# PSDT_Power_v1_0_0.net
KiCad netlist of a schematic drawn in Altium Designer
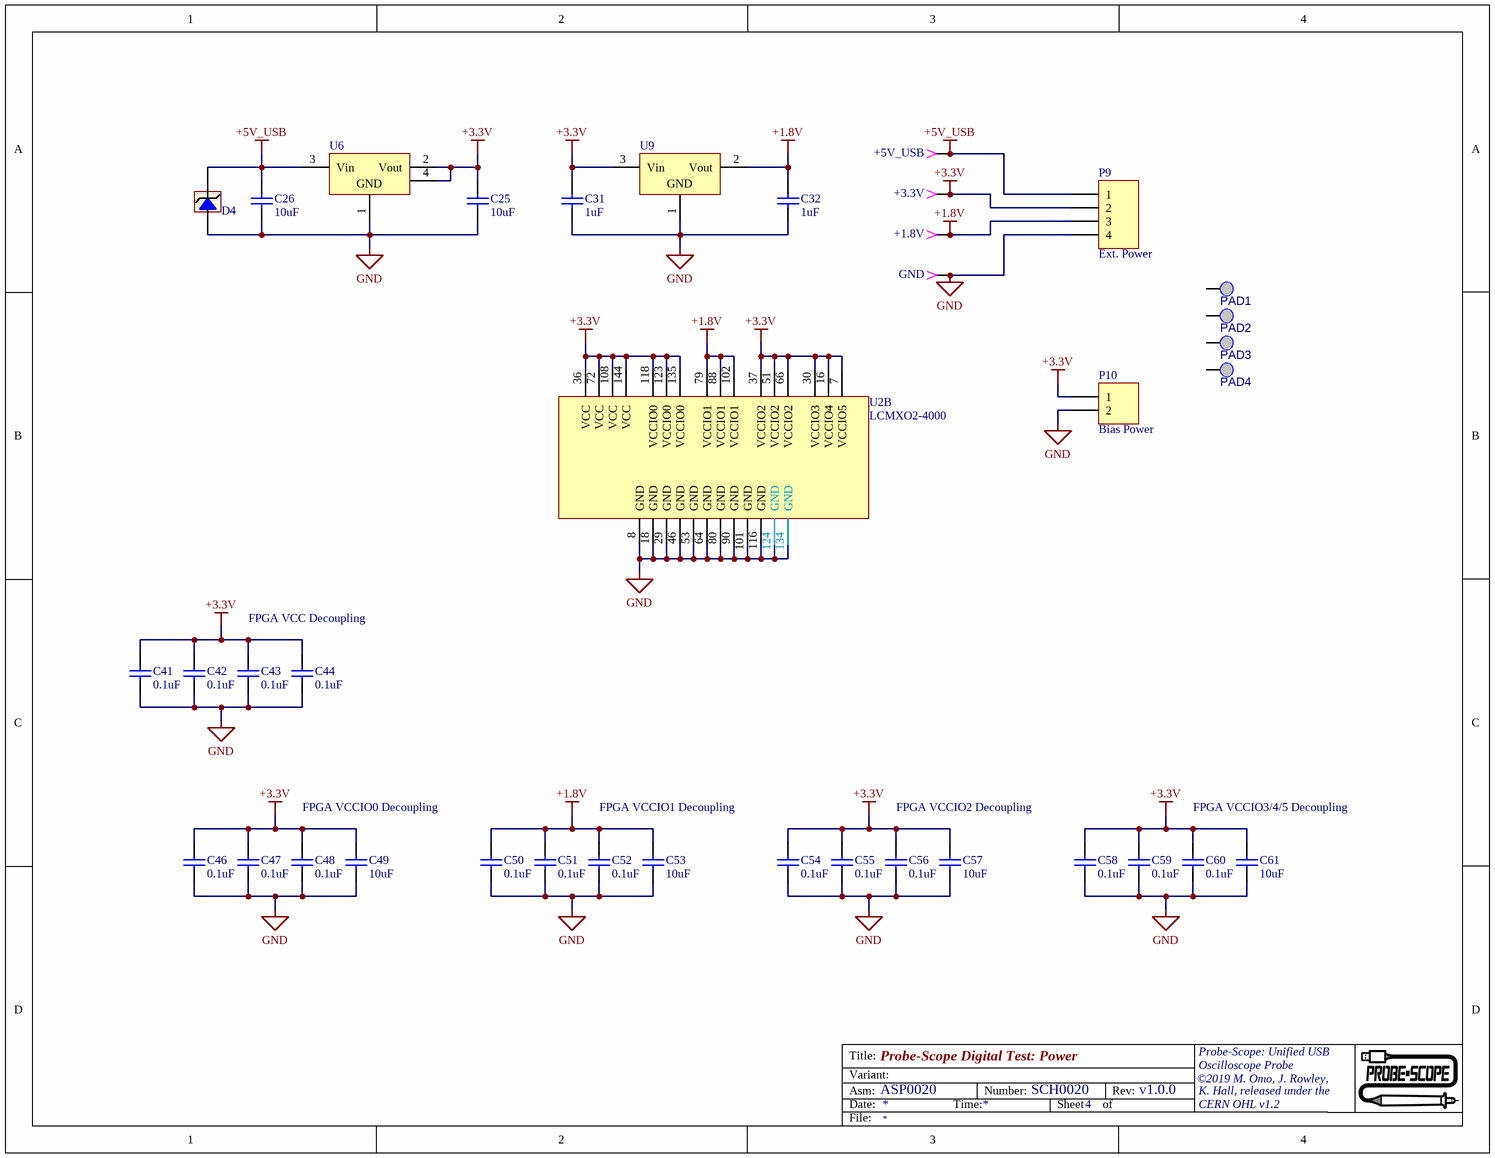
[diagram p0: PSDT Power v1.0.0.SchDoc]

(export (version "E")
  (design (tool "Eeschema 10.0.6"))
  (components
    (comp (ref "+1.8V")
      (value "TP")
      (footprint "TESTPOINT024")
      (fields
        (field (name "MANF") "Keystone Electronics")
        (field (name "APPROVED") "True")
        (field (name "MODIFIED BY") "sotterbacher")
      )
      (libsource (lib "MENG Database Library VPN") (part "TP"))
    )
    (comp (ref "+3.3V")
      (value "TP")
      (footprint "TESTPOINT024")
      (fields
        (field (name "MANF") "Keystone Electronics")
        (field (name "APPROVED") "True")
        (field (name "MODIFIED BY") "sotterbacher")
      )
      (libsource (lib "MENG Database Library VPN") (part "TP"))
    )
    (comp (ref "+5V_USB")
      (value "TP")
      (footprint "TESTPOINT024")
      (fields
        (field (name "MANF") "Keystone Electronics")
        (field (name "APPROVED") "True")
        (field (name "MODIFIED BY") "sotterbacher")
      )
      (libsource (lib "MENG Database Library VPN") (part "TP"))
    )
    (comp (ref "C25")
      (value "10uF")
      (footprint "0603(1608)")
      (fields
        (field (name "MANF") "Samsung Electro-Mechanics")
        (field (name "TOLERANCE") "20")
        (field (name "VOLTAGE") "25")
        (field (name "MODIFIED BY") "sotterbacher")
        (field (name "APPROVED") "True")
      )
      (libsource (lib "MENG Database Library VPN") (part "Cap"))
    )
    (comp (ref "C26")
      (value "10uF")
      (footprint "0603(1608)")
      (fields
        (field (name "MANF") "Samsung Electro-Mechanics")
        (field (name "TOLERANCE") "20")
        (field (name "VOLTAGE") "25")
        (field (name "MODIFIED BY") "sotterbacher")
        (field (name "APPROVED") "True")
      )
      (libsource (lib "MENG Database Library VPN") (part "Cap"))
    )
    (comp (ref "C31")
      (value "1uF")
      (footprint "0402(1005)")
      (fields
        (field (name "MANF") "Murata Electronics")
        (field (name "TOLERANCE") "10")
        (field (name "Comment") "10V")
        (field (name "MODIFIED BY") "jrowley")
        (field (name "APPROVED") "False")
      )
      (libsource (lib "MENG Database Library VPN") (part "Cap"))
    )
    (comp (ref "C32")
      (value "1uF")
      (footprint "0402(1005)")
      (fields
        (field (name "MANF") "Murata Electronics")
        (field (name "TOLERANCE") "10")
        (field (name "Comment") "10V")
        (field (name "MODIFIED BY") "jrowley")
        (field (name "APPROVED") "False")
      )
      (libsource (lib "MENG Database Library VPN") (part "Cap"))
    )
    (comp (ref "C41")
      (value "0.1uF")
      (footprint "0402(1005)")
      (fields
        (field (name "MANF") "Samsung Electro-Mechanics")
        (field (name "TOLERANCE") "10")
        (field (name "VOLTAGE") "6.3")
        (field (name "MODIFIED BY") "jrowley")
        (field (name "APPROVED") "False")
      )
      (libsource (lib "MENG Database Library VPN") (part "Cap"))
    )
    (comp (ref "C42")
      (value "0.1uF")
      (footprint "0402(1005)")
      (fields
        (field (name "MANF") "Samsung Electro-Mechanics")
        (field (name "TOLERANCE") "10")
        (field (name "VOLTAGE") "6.3")
        (field (name "MODIFIED BY") "jrowley")
        (field (name "APPROVED") "False")
      )
      (libsource (lib "MENG Database Library VPN") (part "Cap"))
    )
    (comp (ref "C43")
      (value "0.1uF")
      (footprint "0402(1005)")
      (fields
        (field (name "MANF") "Samsung Electro-Mechanics")
        (field (name "TOLERANCE") "10")
        (field (name "VOLTAGE") "6.3")
        (field (name "MODIFIED BY") "jrowley")
        (field (name "APPROVED") "False")
      )
      (libsource (lib "MENG Database Library VPN") (part "Cap"))
    )
    (comp (ref "C44")
      (value "0.1uF")
      (footprint "0402(1005)")
      (fields
        (field (name "MANF") "Samsung Electro-Mechanics")
        (field (name "TOLERANCE") "10")
        (field (name "VOLTAGE") "6.3")
        (field (name "MODIFIED BY") "jrowley")
        (field (name "APPROVED") "False")
      )
      (libsource (lib "MENG Database Library VPN") (part "Cap"))
    )
    (comp (ref "C46")
      (value "0.1uF")
      (footprint "0402(1005)")
      (fields
        (field (name "MANF") "Samsung Electro-Mechanics")
        (field (name "TOLERANCE") "10")
        (field (name "VOLTAGE") "6.3")
        (field (name "MODIFIED BY") "jrowley")
        (field (name "APPROVED") "False")
      )
      (libsource (lib "MENG Database Library VPN") (part "Cap"))
    )
    (comp (ref "C47")
      (value "0.1uF")
      (footprint "0402(1005)")
      (fields
        (field (name "MANF") "Samsung Electro-Mechanics")
        (field (name "TOLERANCE") "10")
        (field (name "VOLTAGE") "6.3")
        (field (name "MODIFIED BY") "jrowley")
        (field (name "APPROVED") "False")
      )
      (libsource (lib "MENG Database Library VPN") (part "Cap"))
    )
    (comp (ref "C48")
      (value "0.1uF")
      (footprint "0402(1005)")
      (fields
        (field (name "MANF") "Samsung Electro-Mechanics")
        (field (name "TOLERANCE") "10")
        (field (name "VOLTAGE") "6.3")
        (field (name "MODIFIED BY") "jrowley")
        (field (name "APPROVED") "False")
      )
      (libsource (lib "MENG Database Library VPN") (part "Cap"))
    )
    (comp (ref "C49")
      (value "10uF")
      (footprint "0603(1608)")
      (fields
        (field (name "MANF") "Samsung Electro-Mechanics")
        (field (name "TOLERANCE") "20")
        (field (name "VOLTAGE") "25")
        (field (name "MODIFIED BY") "sotterbacher")
        (field (name "APPROVED") "True")
      )
      (libsource (lib "MENG Database Library VPN") (part "Cap"))
    )
    (comp (ref "C50")
      (value "0.1uF")
      (footprint "0402(1005)")
      (fields
        (field (name "MANF") "Samsung Electro-Mechanics")
        (field (name "TOLERANCE") "10")
        (field (name "VOLTAGE") "6.3")
        (field (name "MODIFIED BY") "jrowley")
        (field (name "APPROVED") "False")
      )
      (libsource (lib "MENG Database Library VPN") (part "Cap"))
    )
    (comp (ref "C51")
      (value "0.1uF")
      (footprint "0402(1005)")
      (fields
        (field (name "MANF") "Samsung Electro-Mechanics")
        (field (name "TOLERANCE") "10")
        (field (name "VOLTAGE") "6.3")
        (field (name "MODIFIED BY") "jrowley")
        (field (name "APPROVED") "False")
      )
      (libsource (lib "MENG Database Library VPN") (part "Cap"))
    )
    (comp (ref "C52")
      (value "0.1uF")
      (footprint "0402(1005)")
      (fields
        (field (name "MANF") "Samsung Electro-Mechanics")
        (field (name "TOLERANCE") "10")
        (field (name "VOLTAGE") "6.3")
        (field (name "MODIFIED BY") "jrowley")
        (field (name "APPROVED") "False")
      )
      (libsource (lib "MENG Database Library VPN") (part "Cap"))
    )
    (comp (ref "C53")
      (value "10uF")
      (footprint "0603(1608)")
      (fields
        (field (name "MANF") "Samsung Electro-Mechanics")
        (field (name "TOLERANCE") "20")
        (field (name "VOLTAGE") "25")
        (field (name "MODIFIED BY") "sotterbacher")
        (field (name "APPROVED") "True")
      )
      (libsource (lib "MENG Database Library VPN") (part "Cap"))
    )
    (comp (ref "C54")
      (value "0.1uF")
      (footprint "0402(1005)")
      (fields
        (field (name "MANF") "Samsung Electro-Mechanics")
        (field (name "TOLERANCE") "10")
        (field (name "VOLTAGE") "6.3")
        (field (name "MODIFIED BY") "jrowley")
        (field (name "APPROVED") "False")
      )
      (libsource (lib "MENG Database Library VPN") (part "Cap"))
    )
    (comp (ref "C55")
      (value "0.1uF")
      (footprint "0402(1005)")
      (fields
        (field (name "MANF") "Samsung Electro-Mechanics")
        (field (name "TOLERANCE") "10")
        (field (name "VOLTAGE") "6.3")
        (field (name "MODIFIED BY") "jrowley")
        (field (name "APPROVED") "False")
      )
      (libsource (lib "MENG Database Library VPN") (part "Cap"))
    )
    (comp (ref "C56")
      (value "0.1uF")
      (footprint "0402(1005)")
      (fields
        (field (name "MANF") "Samsung Electro-Mechanics")
        (field (name "TOLERANCE") "10")
        (field (name "VOLTAGE") "6.3")
        (field (name "MODIFIED BY") "jrowley")
        (field (name "APPROVED") "False")
      )
      (libsource (lib "MENG Database Library VPN") (part "Cap"))
    )
    (comp (ref "C57")
      (value "10uF")
      (footprint "0603(1608)")
      (fields
        (field (name "MANF") "Samsung Electro-Mechanics")
        (field (name "TOLERANCE") "20")
        (field (name "VOLTAGE") "25")
        (field (name "MODIFIED BY") "sotterbacher")
        (field (name "APPROVED") "True")
      )
      (libsource (lib "MENG Database Library VPN") (part "Cap"))
    )
    (comp (ref "C58")
      (value "0.1uF")
      (footprint "0402(1005)")
      (fields
        (field (name "MANF") "Samsung Electro-Mechanics")
        (field (name "TOLERANCE") "10")
        (field (name "VOLTAGE") "6.3")
        (field (name "MODIFIED BY") "jrowley")
        (field (name "APPROVED") "False")
      )
      (libsource (lib "MENG Database Library VPN") (part "Cap"))
    )
    (comp (ref "C59")
      (value "0.1uF")
      (footprint "0402(1005)")
      (fields
        (field (name "MANF") "Samsung Electro-Mechanics")
        (field (name "TOLERANCE") "10")
        (field (name "VOLTAGE") "6.3")
        (field (name "MODIFIED BY") "jrowley")
        (field (name "APPROVED") "False")
      )
      (libsource (lib "MENG Database Library VPN") (part "Cap"))
    )
    (comp (ref "C60")
      (value "0.1uF")
      (footprint "0402(1005)")
      (fields
        (field (name "MANF") "Samsung Electro-Mechanics")
        (field (name "TOLERANCE") "10")
        (field (name "VOLTAGE") "6.3")
        (field (name "MODIFIED BY") "jrowley")
        (field (name "APPROVED") "False")
      )
      (libsource (lib "MENG Database Library VPN") (part "Cap"))
    )
    (comp (ref "C61")
      (value "10uF")
      (footprint "0603(1608)")
      (fields
        (field (name "MANF") "Samsung Electro-Mechanics")
        (field (name "TOLERANCE") "20")
        (field (name "VOLTAGE") "25")
        (field (name "MODIFIED BY") "sotterbacher")
        (field (name "APPROVED") "True")
      )
      (libsource (lib "MENG Database Library VPN") (part "Cap"))
    )
    (comp (ref "D4")
      (value "6.5V")
      (footprint "SMB NP")
      (fields
        (field (name "MANF") "Littelfuse")
        (field (name "VOLTAGE") "6.5")
        (field (name "POWER") "600")
        (field (name "MODIFIED BY") "tgage")
        (field (name "APPROVED") "True")
      )
      (libsource (lib "MENG Database Library VPN") (part "Transzorb"))
    )
    (comp (ref "GND")
      (value "TP")
      (footprint "TESTPOINT024")
      (fields
        (field (name "MANF") "Keystone Electronics")
        (field (name "MODIFIED BY") "sotterbacher")
        (field (name "APPROVED") "True")
      )
      (libsource (lib "MENG Database Library VPN") (part "TP"))
    )
    (comp (ref "P9")
      (value "Ext. Power")
      (footprint "0.1HDR1X4P")
      (fields
        (field (name "MANF") "Molex")
        (field (name "VOLTAGE") "250")
        (field (name "MODIFIED BY") "jrowley")
        (field (name "APPROVED") "False")
      )
      (libsource (lib "MENG Database Library VPN") (part "Header 4"))
    )
    (comp (ref "P10")
      (value "Bias Power")
      (footprint "0.1HDR1X2P")
      (fields
        (field (name "MANF") "Molex")
        (field (name "VOLTAGE") "250")
        (field (name "MODIFIED BY") "jrowley")
        (field (name "APPROVED") "False")
      )
      (libsource (lib "MENG Database Library VPN") (part "Header 2"))
    )
    (comp (ref "PAD1")
      (value "4-40 Loose")
      (footprint "PAD-4-40 Loose")
      (fields
        (field (name "MANF") "dummy")
        (field (name "MODIFIED BY") "pmarcus")
        (field (name "APPROVED") "True")
      )
      (libsource (lib "MENG Database Library VPN") (part "PAD"))
    )
    (comp (ref "PAD2")
      (value "4-40 Loose")
      (footprint "PAD-4-40 Loose")
      (fields
        (field (name "MANF") "dummy")
        (field (name "MODIFIED BY") "pmarcus")
        (field (name "APPROVED") "True")
      )
      (libsource (lib "MENG Database Library VPN") (part "PAD"))
    )
    (comp (ref "PAD3")
      (value "4-40 Loose")
      (footprint "PAD-4-40 Loose")
      (fields
        (field (name "MANF") "dummy")
        (field (name "MODIFIED BY") "pmarcus")
        (field (name "APPROVED") "True")
      )
      (libsource (lib "MENG Database Library VPN") (part "PAD"))
    )
    (comp (ref "PAD4")
      (value "4-40 Loose")
      (footprint "PAD-4-40 Loose")
      (fields
        (field (name "MANF") "dummy")
        (field (name "MODIFIED BY") "pmarcus")
        (field (name "APPROVED") "True")
      )
      (libsource (lib "MENG Database Library VPN") (part "PAD"))
    )
    (comp (ref "U2")
      (value "LCMXO2-4000")
      (footprint "UL_TQFP144")
      (fields (field (name "MANF") "Lattice Semiconductor Corporation"))
      (libsource (lib "PS") (part "MachXO2-4000-TG144"))
    )
    (comp (ref "U6")
      (value "LD1086D2M33TR")
      (footprint "D2PAK TO263-4N")
      (fields
        (field (name "MANF") "ST Microelectronics")
        (field (name "MODIFIED BY") "cschneiker")
        (field (name "APPROVED") "True")
      )
      (libsource (lib "MENG Database Library VPN") (part "Volt Reg 4"))
    )
    (comp (ref "U9")
      (value "1.8V")
      (footprint "SOT23-12-3TOP")
      (fields
        (field (name "MANF") "Microchip")
        (field (name "MODIFIED BY") "jrowley")
        (field (name "APPROVED") "False")
      )
      (libsource (lib "MENG Database Library VPN") (part "Volt Reg 7"))
    )
  )
  (nets
    (net (code "1") (name "+1.8V") (class "Default")
      (node (ref "+1.8V") (pin "1") (pinfunction "1_1") (pintype "passive"))
      (node (ref "C32") (pin "2") (pinfunction "2_2") (pintype "passive"))
      (node (ref "C50") (pin "2") (pinfunction "2_2") (pintype "passive"))
      (node (ref "C51") (pin "2") (pinfunction "2_2") (pintype "passive"))
      (node (ref "C52") (pin "2") (pinfunction "2_2") (pintype "passive"))
      (node (ref "C53") (pin "2") (pinfunction "2_2") (pintype "passive"))
      (node (ref "P9") (pin "3") (pinfunction "3_3") (pintype "passive"))
      (node (ref "U2") (pin "102") (pinfunction "VCCIO1_102") (pintype "power_in"))
      (node (ref "U2") (pin "79") (pinfunction "VCCIO1_79") (pintype "power_in"))
      (node (ref "U2") (pin "88") (pinfunction "VCCIO1_88") (pintype "power_in"))
      (node (ref "U9") (pin "2") (pinfunction "Vout_2") (pintype "passive"))
    )
    (net (code "2") (name "+3.3V") (class "Default")
      (node (ref "+3.3V") (pin "1") (pinfunction "1_1") (pintype "passive"))
      (node (ref "C25") (pin "2") (pinfunction "2_2") (pintype "passive"))
      (node (ref "C31") (pin "2") (pinfunction "2_2") (pintype "passive"))
      (node (ref "C41") (pin "2") (pinfunction "2_2") (pintype "passive"))
      (node (ref "C42") (pin "2") (pinfunction "2_2") (pintype "passive"))
      (node (ref "C43") (pin "2") (pinfunction "2_2") (pintype "passive"))
      (node (ref "C44") (pin "2") (pinfunction "2_2") (pintype "passive"))
      (node (ref "C46") (pin "2") (pinfunction "2_2") (pintype "passive"))
      (node (ref "C47") (pin "2") (pinfunction "2_2") (pintype "passive"))
      (node (ref "C48") (pin "2") (pinfunction "2_2") (pintype "passive"))
      (node (ref "C49") (pin "2") (pinfunction "2_2") (pintype "passive"))
      (node (ref "C54") (pin "2") (pinfunction "2_2") (pintype "passive"))
      (node (ref "C55") (pin "2") (pinfunction "2_2") (pintype "passive"))
      (node (ref "C56") (pin "2") (pinfunction "2_2") (pintype "passive"))
      (node (ref "C57") (pin "2") (pinfunction "2_2") (pintype "passive"))
      (node (ref "C58") (pin "2") (pinfunction "2_2") (pintype "passive"))
      (node (ref "C59") (pin "2") (pinfunction "2_2") (pintype "passive"))
      (node (ref "C60") (pin "2") (pinfunction "2_2") (pintype "passive"))
      (node (ref "C61") (pin "2") (pinfunction "2_2") (pintype "passive"))
      (node (ref "P10") (pin "1") (pinfunction "1_1") (pintype "passive"))
      (node (ref "P9") (pin "2") (pinfunction "2_2") (pintype "passive"))
      (node (ref "U2") (pin "108") (pinfunction "VCC_108") (pintype "power_in"))
      (node (ref "U2") (pin "118") (pinfunction "VCCIO0_118") (pintype "power_in"))
      (node (ref "U2") (pin "123") (pinfunction "VCCIO0_123") (pintype "power_in"))
      (node (ref "U2") (pin "135") (pinfunction "VCCIO0_135") (pintype "power_in"))
      (node (ref "U2") (pin "144") (pinfunction "VCC_144") (pintype "power_in"))
      (node (ref "U2") (pin "16") (pinfunction "VCCIO4_16") (pintype "power_in"))
      (node (ref "U2") (pin "30") (pinfunction "VCCIO3_30") (pintype "power_in"))
      (node (ref "U2") (pin "36") (pinfunction "VCC_36") (pintype "power_in"))
      (node (ref "U2") (pin "37") (pinfunction "VCCIO2_37") (pintype "power_in"))
      (node (ref "U2") (pin "51") (pinfunction "VCCIO2_51") (pintype "power_in"))
      (node (ref "U2") (pin "66") (pinfunction "VCCIO2_66") (pintype "power_in"))
      (node (ref "U2") (pin "7") (pinfunction "VCCIO5_7") (pintype "power_in"))
      (node (ref "U2") (pin "72") (pinfunction "VCC_72") (pintype "power_in"))
      (node (ref "U6") (pin "2") (pinfunction "Vout_2") (pintype "passive"))
      (node (ref "U6") (pin "4") (pinfunction "GND_4") (pintype "passive"))
      (node (ref "U9") (pin "3") (pinfunction "Vin_3") (pintype "passive"))
    )
    (net (code "3") (name "+5V_USB") (class "Default")
      (node (ref "+5V_USB") (pin "1") (pinfunction "1_1") (pintype "passive"))
      (node (ref "C26") (pin "2") (pinfunction "2_2") (pintype "passive"))
      (node (ref "D4") (pin "2") (pinfunction "2_2") (pintype "passive"))
      (node (ref "P9") (pin "1") (pinfunction "1_1") (pintype "passive"))
      (node (ref "U6") (pin "3") (pinfunction "Vin_3") (pintype "passive"))
    )
    (net (code "4") (name "GND") (class "Default")
      (node (ref "C25") (pin "1") (pinfunction "1_1") (pintype "passive"))
      (node (ref "C26") (pin "1") (pinfunction "1_1") (pintype "passive"))
      (node (ref "C31") (pin "1") (pinfunction "1_1") (pintype "passive"))
      (node (ref "C32") (pin "1") (pinfunction "1_1") (pintype "passive"))
      (node (ref "C41") (pin "1") (pinfunction "1_1") (pintype "passive"))
      (node (ref "C42") (pin "1") (pinfunction "1_1") (pintype "passive"))
      (node (ref "C43") (pin "1") (pinfunction "1_1") (pintype "passive"))
      (node (ref "C44") (pin "1") (pinfunction "1_1") (pintype "passive"))
      (node (ref "C46") (pin "1") (pinfunction "1_1") (pintype "passive"))
      (node (ref "C47") (pin "1") (pinfunction "1_1") (pintype "passive"))
      (node (ref "C48") (pin "1") (pinfunction "1_1") (pintype "passive"))
      (node (ref "C49") (pin "1") (pinfunction "1_1") (pintype "passive"))
      (node (ref "C50") (pin "1") (pinfunction "1_1") (pintype "passive"))
      (node (ref "C51") (pin "1") (pinfunction "1_1") (pintype "passive"))
      (node (ref "C52") (pin "1") (pinfunction "1_1") (pintype "passive"))
      (node (ref "C53") (pin "1") (pinfunction "1_1") (pintype "passive"))
      (node (ref "C54") (pin "1") (pinfunction "1_1") (pintype "passive"))
      (node (ref "C55") (pin "1") (pinfunction "1_1") (pintype "passive"))
      (node (ref "C56") (pin "1") (pinfunction "1_1") (pintype "passive"))
      (node (ref "C57") (pin "1") (pinfunction "1_1") (pintype "passive"))
      (node (ref "C58") (pin "1") (pinfunction "1_1") (pintype "passive"))
      (node (ref "C59") (pin "1") (pinfunction "1_1") (pintype "passive"))
      (node (ref "C60") (pin "1") (pinfunction "1_1") (pintype "passive"))
      (node (ref "C61") (pin "1") (pinfunction "1_1") (pintype "passive"))
      (node (ref "D4") (pin "1") (pinfunction "1_1") (pintype "passive"))
      (node (ref "GND") (pin "1") (pinfunction "1_1") (pintype "passive"))
      (node (ref "P10") (pin "2") (pinfunction "2_2") (pintype "passive"))
      (node (ref "P9") (pin "4") (pinfunction "4_4") (pintype "passive"))
      (node (ref "U2") (pin "101") (pinfunction "GND_101") (pintype "power_in"))
      (node (ref "U2") (pin "116") (pinfunction "GND_116") (pintype "power_in"))
      (node (ref "U2") (pin "124") (pinfunction "GND_124") (pintype "power_in"))
      (node (ref "U2") (pin "134") (pinfunction "GND_134") (pintype "power_in"))
      (node (ref "U2") (pin "18") (pinfunction "GND_18") (pintype "power_in"))
      (node (ref "U2") (pin "29") (pinfunction "GND_29") (pintype "power_in"))
      (node (ref "U2") (pin "46") (pinfunction "GND_46") (pintype "power_in"))
      (node (ref "U2") (pin "53") (pinfunction "GND_53") (pintype "power_in"))
      (node (ref "U2") (pin "64") (pinfunction "GND_64") (pintype "power_in"))
      (node (ref "U2") (pin "8") (pinfunction "GND_8") (pintype "power_in"))
      (node (ref "U2") (pin "80") (pinfunction "GND_80") (pintype "power_in"))
      (node (ref "U2") (pin "90") (pinfunction "GND_90") (pintype "power_in"))
      (node (ref "U6") (pin "1") (pinfunction "GND_1") (pintype "passive"))
      (node (ref "U9") (pin "1") (pinfunction "GND_1") (pintype "passive"))
    )
    (net (code "5") (name "unconnected-(PAD1-Pad1)") (class "Default")
      (node (ref "PAD1") (pin "1") (pintype "passive"))
    )
    (net (code "6") (name "unconnected-(PAD2-Pad1)") (class "Default")
      (node (ref "PAD2") (pin "1") (pintype "passive"))
    )
    (net (code "7") (name "unconnected-(PAD3-Pad1)") (class "Default")
      (node (ref "PAD3") (pin "1") (pintype "passive"))
    )
    (net (code "8") (name "unconnected-(PAD4-Pad1)") (class "Default")
      (node (ref "PAD4") (pin "1") (pintype "passive"))
    )
  )
)
